# OhmMeter.net
KiCad netlist of a schematic drawn in EAGLE
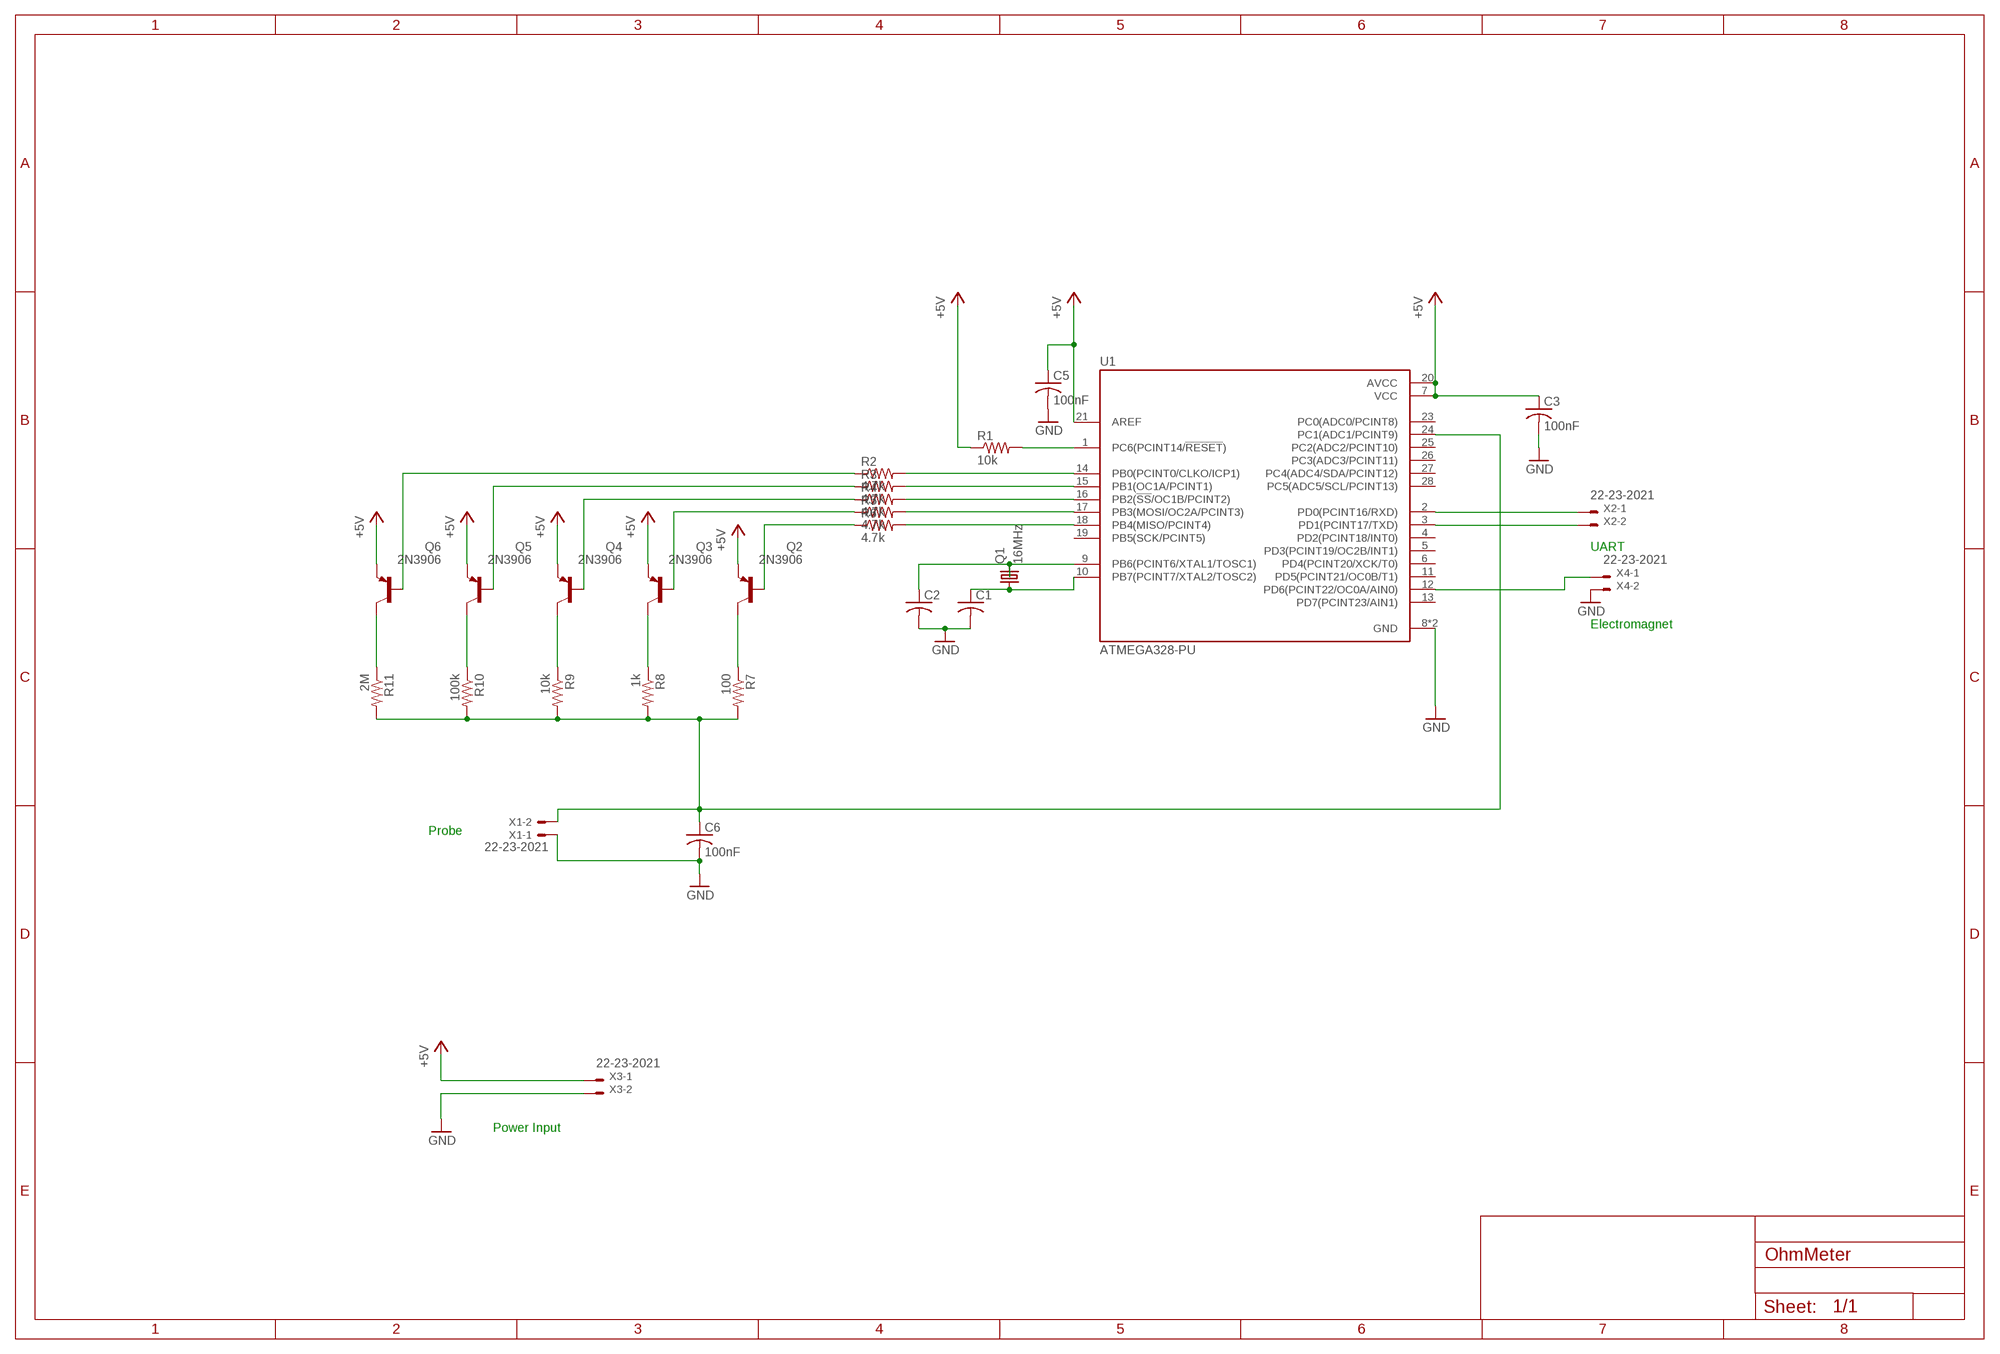
[diagram p0: schematic, sheet 1]

(export (version "E")
  (design (tool "Eeschema 10.0.6"))
  (components
    (comp (ref "C1")
      (value "C-US025-024X044")
      (footprint "eagle-import:C025-024X044")
      (libsource (lib "eagle-import") (part "C-US025-024X044"))
    )
    (comp (ref "C2")
      (value "C-US025-024X044")
      (footprint "eagle-import:C025-024X044")
      (libsource (lib "eagle-import") (part "C-US025-024X044"))
    )
    (comp (ref "C3")
      (value "100nF")
      (footprint "eagle-import:C025-024X044")
      (libsource (lib "eagle-import") (part "C-US025-024X044"))
    )
    (comp (ref "C5")
      (value "100nF")
      (footprint "eagle-import:C025-024X044")
      (libsource (lib "eagle-import") (part "C-US025-024X044"))
    )
    (comp (ref "C6")
      (value "100nF")
      (footprint "eagle-import:C025-024X044")
      (libsource (lib "eagle-import") (part "C-US025-024X044"))
    )
    (comp (ref "Q1")
      (value "16MHz")
      (footprint "eagle-import:HC49_S")
      (libsource (lib "eagle-import") (part "CRYSTALHC49S"))
    )
    (comp (ref "Q2")
      (value "2N3906")
      (footprint "eagle-import:TO92")
      (libsource (lib "eagle-import") (part "2N3906"))
    )
    (comp (ref "Q3")
      (value "2N3906")
      (footprint "eagle-import:TO92")
      (libsource (lib "eagle-import") (part "2N3906"))
    )
    (comp (ref "Q4")
      (value "2N3906")
      (footprint "eagle-import:TO92")
      (libsource (lib "eagle-import") (part "2N3906"))
    )
    (comp (ref "Q5")
      (value "2N3906")
      (footprint "eagle-import:TO92")
      (libsource (lib "eagle-import") (part "2N3906"))
    )
    (comp (ref "Q6")
      (value "2N3906")
      (footprint "eagle-import:TO92")
      (libsource (lib "eagle-import") (part "2N3906"))
    )
    (comp (ref "R1")
      (value "10k")
      (footprint "eagle-import:0204_5")
      (libsource (lib "eagle-import") (part "R-US_0204/5"))
    )
    (comp (ref "R2")
      (value "4.7k")
      (footprint "eagle-import:0204_5")
      (libsource (lib "eagle-import") (part "R-US_0204/5"))
    )
    (comp (ref "R3")
      (value "4.7k")
      (footprint "eagle-import:0204_5")
      (libsource (lib "eagle-import") (part "R-US_0204/5"))
    )
    (comp (ref "R4")
      (value "4.7k")
      (footprint "eagle-import:0204_5")
      (libsource (lib "eagle-import") (part "R-US_0204/5"))
    )
    (comp (ref "R5")
      (value "4.7k")
      (footprint "eagle-import:0204_5")
      (libsource (lib "eagle-import") (part "R-US_0204/5"))
    )
    (comp (ref "R6")
      (value "4.7k")
      (footprint "eagle-import:0204_5")
      (libsource (lib "eagle-import") (part "R-US_0204/5"))
    )
    (comp (ref "R7")
      (value "100")
      (footprint "eagle-import:0204_5")
      (libsource (lib "eagle-import") (part "R-US_0204/5"))
    )
    (comp (ref "R8")
      (value "1k")
      (footprint "eagle-import:0204_5")
      (libsource (lib "eagle-import") (part "R-US_0204/5"))
    )
    (comp (ref "R9")
      (value "10k")
      (footprint "eagle-import:0204_5")
      (libsource (lib "eagle-import") (part "R-US_0204/5"))
    )
    (comp (ref "R10")
      (value "100k")
      (footprint "eagle-import:0204_5")
      (libsource (lib "eagle-import") (part "R-US_0204/5"))
    )
    (comp (ref "R11")
      (value "2M")
      (footprint "eagle-import:0204_5")
      (libsource (lib "eagle-import") (part "R-US_0204/5"))
    )
    (comp (ref "U1")
      (value "ATMEGA328-PU")
      (footprint "eagle-import:DIP787W46P254L3467H508Q28")
      (fields (field (name "MF") "Microchip Technology"))
      (libsource (lib "eagle-import") (part "ATMEGA328-PU"))
    )
    (comp (ref "X1")
      (value "22-23-2021")
      (footprint "eagle-import:22-23-2021")
      (fields (field (name "MF") "MOLEX"))
      (libsource (lib "eagle-import") (part "22-23-2021"))
    )
    (comp (ref "X2")
      (value "22-23-2021")
      (footprint "eagle-import:22-23-2021")
      (fields (field (name "MF") "MOLEX"))
      (libsource (lib "eagle-import") (part "22-23-2021"))
    )
    (comp (ref "X3")
      (value "22-23-2021")
      (footprint "eagle-import:22-23-2021")
      (fields (field (name "MF") "MOLEX"))
      (libsource (lib "eagle-import") (part "22-23-2021"))
    )
    (comp (ref "X4")
      (value "22-23-2021")
      (footprint "eagle-import:22-23-2021")
      (fields (field (name "MF") "MOLEX"))
      (libsource (lib "eagle-import") (part "22-23-2021"))
    )
  )
  (nets
    (net (code "1") (name "+5V") (class "Default")
      (node (ref "C3") (pin "1") (pinfunction "1_1") (pintype "passive"))
      (node (ref "C5") (pin "1") (pinfunction "1_1") (pintype "passive"))
      (node (ref "Q2") (pin "3") (pinfunction "E_3") (pintype "passive"))
      (node (ref "Q3") (pin "3") (pinfunction "E_3") (pintype "passive"))
      (node (ref "Q4") (pin "3") (pinfunction "E_3") (pintype "passive"))
      (node (ref "Q5") (pin "3") (pinfunction "E_3") (pintype "passive"))
      (node (ref "Q6") (pin "3") (pinfunction "E_3") (pintype "passive"))
      (node (ref "R1") (pin "1") (pinfunction "1_1") (pintype "passive"))
      (node (ref "U1") (pin "20") (pinfunction "AVCC_20") (pintype "power_in"))
      (node (ref "U1") (pin "21") (pinfunction "AREF_21") (pintype "input"))
      (node (ref "U1") (pin "7") (pinfunction "VCC_7") (pintype "power_in"))
      (node (ref "X3") (pin "1") (pinfunction "S_1") (pintype "passive"))
    )
    (net (code "2") (name "GND") (class "Default")
      (node (ref "C1") (pin "2") (pinfunction "2_2") (pintype "passive"))
      (node (ref "C2") (pin "2") (pinfunction "2_2") (pintype "passive"))
      (node (ref "C3") (pin "2") (pinfunction "2_2") (pintype "passive"))
      (node (ref "C5") (pin "2") (pinfunction "2_2") (pintype "passive"))
      (node (ref "C6") (pin "2") (pinfunction "2_2") (pintype "passive"))
      (node (ref "U1") (pin "22") (pinfunction "GND_22") (pintype "power_in"))
      (node (ref "U1") (pin "8") (pinfunction "GND_8") (pintype "power_in"))
      (node (ref "X1") (pin "1") (pinfunction "S_1") (pintype "passive"))
      (node (ref "X3") (pin "2") (pinfunction "S_2") (pintype "passive"))
      (node (ref "X4") (pin "2") (pinfunction "S_2") (pintype "passive"))
    )
    (net (code "3") (name "Net-(Q2-B)") (class "Default")
      (node (ref "Q2") (pin "2") (pinfunction "B_2") (pintype "passive"))
      (node (ref "R6") (pin "1") (pinfunction "1_1") (pintype "passive"))
    )
    (net (code "4") (name "Net-(Q2-C)") (class "Default")
      (node (ref "Q2") (pin "1") (pinfunction "C_1") (pintype "passive"))
      (node (ref "R7") (pin "1") (pinfunction "1_1") (pintype "passive"))
    )
    (net (code "5") (name "Net-(Q3-B)") (class "Default")
      (node (ref "Q3") (pin "2") (pinfunction "B_2") (pintype "passive"))
      (node (ref "R5") (pin "1") (pinfunction "1_1") (pintype "passive"))
    )
    (net (code "6") (name "Net-(Q3-C)") (class "Default")
      (node (ref "Q3") (pin "1") (pinfunction "C_1") (pintype "passive"))
      (node (ref "R8") (pin "1") (pinfunction "1_1") (pintype "passive"))
    )
    (net (code "7") (name "Net-(Q4-B)") (class "Default")
      (node (ref "Q4") (pin "2") (pinfunction "B_2") (pintype "passive"))
      (node (ref "R4") (pin "1") (pinfunction "1_1") (pintype "passive"))
    )
    (net (code "8") (name "Net-(Q4-C)") (class "Default")
      (node (ref "Q4") (pin "1") (pinfunction "C_1") (pintype "passive"))
      (node (ref "R9") (pin "1") (pinfunction "1_1") (pintype "passive"))
    )
    (net (code "9") (name "Net-(Q5-B)") (class "Default")
      (node (ref "Q5") (pin "2") (pinfunction "B_2") (pintype "passive"))
      (node (ref "R3") (pin "1") (pinfunction "1_1") (pintype "passive"))
    )
    (net (code "10") (name "Net-(Q5-C)") (class "Default")
      (node (ref "Q5") (pin "1") (pinfunction "C_1") (pintype "passive"))
      (node (ref "R10") (pin "1") (pinfunction "1_1") (pintype "passive"))
    )
    (net (code "11") (name "Net-(Q6-B)") (class "Default")
      (node (ref "Q6") (pin "2") (pinfunction "B_2") (pintype "passive"))
      (node (ref "R2") (pin "1") (pinfunction "1_1") (pintype "passive"))
    )
    (net (code "12") (name "Net-(Q6-C)") (class "Default")
      (node (ref "Q6") (pin "1") (pinfunction "C_1") (pintype "passive"))
      (node (ref "R11") (pin "1") (pinfunction "1_1") (pintype "passive"))
    )
    (net (code "13") (name "Net-(U1-PB0(PCINT0{slash}CLKO{slash}ICP1))") (class "Default")
      (node (ref "R2") (pin "2") (pinfunction "2_2") (pintype "passive"))
      (node (ref "U1") (pin "14") (pinfunction "PB0(PCINT0/CLKO/ICP1)_14") (pintype "bidirectional"))
    )
    (net (code "14") (name "Net-(U1-PB1(OC1A{slash}PCINT1))") (class "Default")
      (node (ref "R3") (pin "2") (pinfunction "2_2") (pintype "passive"))
      (node (ref "U1") (pin "15") (pinfunction "PB1(OC1A/PCINT1)_15") (pintype "bidirectional"))
    )
    (net (code "15") (name "Net-(U1-PB2(~{SS}{slash}OC1B{slash}PCINT2))") (class "Default")
      (node (ref "R4") (pin "2") (pinfunction "2_2") (pintype "passive"))
      (node (ref "U1") (pin "16") (pinfunction "PB2(~{SS}/OC1B/PCINT2)_16") (pintype "bidirectional"))
    )
    (net (code "16") (name "Net-(U1-PB3(MOSI{slash}OC2A{slash}PCINT3))") (class "Default")
      (node (ref "R5") (pin "2") (pinfunction "2_2") (pintype "passive"))
      (node (ref "U1") (pin "17") (pinfunction "PB3(MOSI/OC2A/PCINT3)_17") (pintype "bidirectional"))
    )
    (net (code "17") (name "Net-(U1-PB4(MISO{slash}PCINT4))") (class "Default")
      (node (ref "R6") (pin "2") (pinfunction "2_2") (pintype "passive"))
      (node (ref "U1") (pin "18") (pinfunction "PB4(MISO/PCINT4)_18") (pintype "bidirectional"))
    )
    (net (code "18") (name "Net-(U1-PB6(PCINT6{slash}XTAL1{slash}TOSC1))") (class "Default")
      (node (ref "C2") (pin "1") (pinfunction "1_1") (pintype "passive"))
      (node (ref "Q1") (pin "2") (pinfunction "2_2") (pintype "passive"))
      (node (ref "U1") (pin "9") (pinfunction "PB6(PCINT6/XTAL1/TOSC1)_9") (pintype "bidirectional"))
    )
    (net (code "19") (name "Net-(U1-PB7(PCINT7{slash}XTAL2{slash}TOSC2))") (class "Default")
      (node (ref "C1") (pin "1") (pinfunction "1_1") (pintype "passive"))
      (node (ref "Q1") (pin "1") (pinfunction "1_1") (pintype "passive"))
      (node (ref "U1") (pin "10") (pinfunction "PB7(PCINT7/XTAL2/TOSC2)_10") (pintype "bidirectional"))
    )
    (net (code "20") (name "Net-(U1-PC1(ADC1{slash}PCINT9))") (class "Default")
      (node (ref "C6") (pin "1") (pinfunction "1_1") (pintype "passive"))
      (node (ref "R10") (pin "2") (pinfunction "2_2") (pintype "passive"))
      (node (ref "R11") (pin "2") (pinfunction "2_2") (pintype "passive"))
      (node (ref "R7") (pin "2") (pinfunction "2_2") (pintype "passive"))
      (node (ref "R8") (pin "2") (pinfunction "2_2") (pintype "passive"))
      (node (ref "R9") (pin "2") (pinfunction "2_2") (pintype "passive"))
      (node (ref "U1") (pin "24") (pinfunction "PC1(ADC1/PCINT9)_24") (pintype "bidirectional"))
      (node (ref "X1") (pin "2") (pinfunction "S_2") (pintype "passive"))
    )
    (net (code "21") (name "Net-(U1-PC6(PCINT14{slash}~{RESET}))") (class "Default")
      (node (ref "R1") (pin "2") (pinfunction "2_2") (pintype "passive"))
      (node (ref "U1") (pin "1") (pinfunction "PC6(PCINT14/~{RESET})_1") (pintype "bidirectional"))
    )
    (net (code "22") (name "Net-(U1-PD0(PCINT16{slash}RXD))") (class "Default")
      (node (ref "U1") (pin "2") (pinfunction "PD0(PCINT16/RXD)_2") (pintype "bidirectional"))
      (node (ref "X2") (pin "1") (pinfunction "S_1") (pintype "passive"))
    )
    (net (code "23") (name "Net-(U1-PD1(PCINT17{slash}TXD))") (class "Default")
      (node (ref "U1") (pin "3") (pinfunction "PD1(PCINT17/TXD)_3") (pintype "bidirectional"))
      (node (ref "X2") (pin "2") (pinfunction "S_2") (pintype "passive"))
    )
    (net (code "24") (name "Net-(U1-PD6(PCINT22{slash}OC0A{slash}AIN0))") (class "Default")
      (node (ref "U1") (pin "12") (pinfunction "PD6(PCINT22/OC0A/AIN0)_12") (pintype "bidirectional"))
      (node (ref "X4") (pin "1") (pinfunction "S_1") (pintype "passive"))
    )
    (net (code "25") (name "unconnected-(U1-PB5(SCK{slash}PCINT5)-Pad19)") (class "Default")
      (node (ref "U1") (pin "19") (pinfunction "PB5(SCK/PCINT5)_19") (pintype "bidirectional"))
    )
    (net (code "26") (name "unconnected-(U1-PC0(ADC0{slash}PCINT8)-Pad23)") (class "Default")
      (node (ref "U1") (pin "23") (pinfunction "PC0(ADC0/PCINT8)_23") (pintype "bidirectional"))
    )
    (net (code "27") (name "unconnected-(U1-PC2(ADC2{slash}PCINT10)-Pad25)") (class "Default")
      (node (ref "U1") (pin "25") (pinfunction "PC2(ADC2/PCINT10)_25") (pintype "bidirectional"))
    )
    (net (code "28") (name "unconnected-(U1-PC3(ADC3{slash}PCINT11)-Pad26)") (class "Default")
      (node (ref "U1") (pin "26") (pinfunction "PC3(ADC3/PCINT11)_26") (pintype "bidirectional"))
    )
    (net (code "29") (name "unconnected-(U1-PC4(ADC4{slash}SDA{slash}PCINT12)-Pad27)") (class "Default")
      (node (ref "U1") (pin "27") (pinfunction "PC4(ADC4/SDA/PCINT12)_27") (pintype "bidirectional"))
    )
    (net (code "30") (name "unconnected-(U1-PC5(ADC5{slash}SCL{slash}PCINT13)-Pad28)") (class "Default")
      (node (ref "U1") (pin "28") (pinfunction "PC5(ADC5/SCL/PCINT13)_28") (pintype "bidirectional"))
    )
    (net (code "31") (name "unconnected-(U1-PD2(PCINT18{slash}INT0)-Pad4)") (class "Default")
      (node (ref "U1") (pin "4") (pinfunction "PD2(PCINT18/INT0)_4") (pintype "bidirectional"))
    )
    (net (code "32") (name "unconnected-(U1-PD3(PCINT19{slash}OC2B{slash}INT1)-Pad5)") (class "Default")
      (node (ref "U1") (pin "5") (pinfunction "PD3(PCINT19/OC2B/INT1)_5") (pintype "bidirectional"))
    )
    (net (code "33") (name "unconnected-(U1-PD4(PCINT20{slash}XCK{slash}T0)-Pad6)") (class "Default")
      (node (ref "U1") (pin "6") (pinfunction "PD4(PCINT20/XCK/T0)_6") (pintype "bidirectional"))
    )
    (net (code "34") (name "unconnected-(U1-PD5(PCINT21{slash}OC0B{slash}T1)-Pad11)") (class "Default")
      (node (ref "U1") (pin "11") (pinfunction "PD5(PCINT21/OC0B/T1)_11") (pintype "bidirectional"))
    )
    (net (code "35") (name "unconnected-(U1-PD7(PCINT23{slash}AIN1)-Pad13)") (class "Default")
      (node (ref "U1") (pin "13") (pinfunction "PD7(PCINT23/AIN1)_13") (pintype "bidirectional"))
    )
  )
)
